# 32u4_devboard_v10.net
KiCad netlist of a schematic drawn in EAGLE
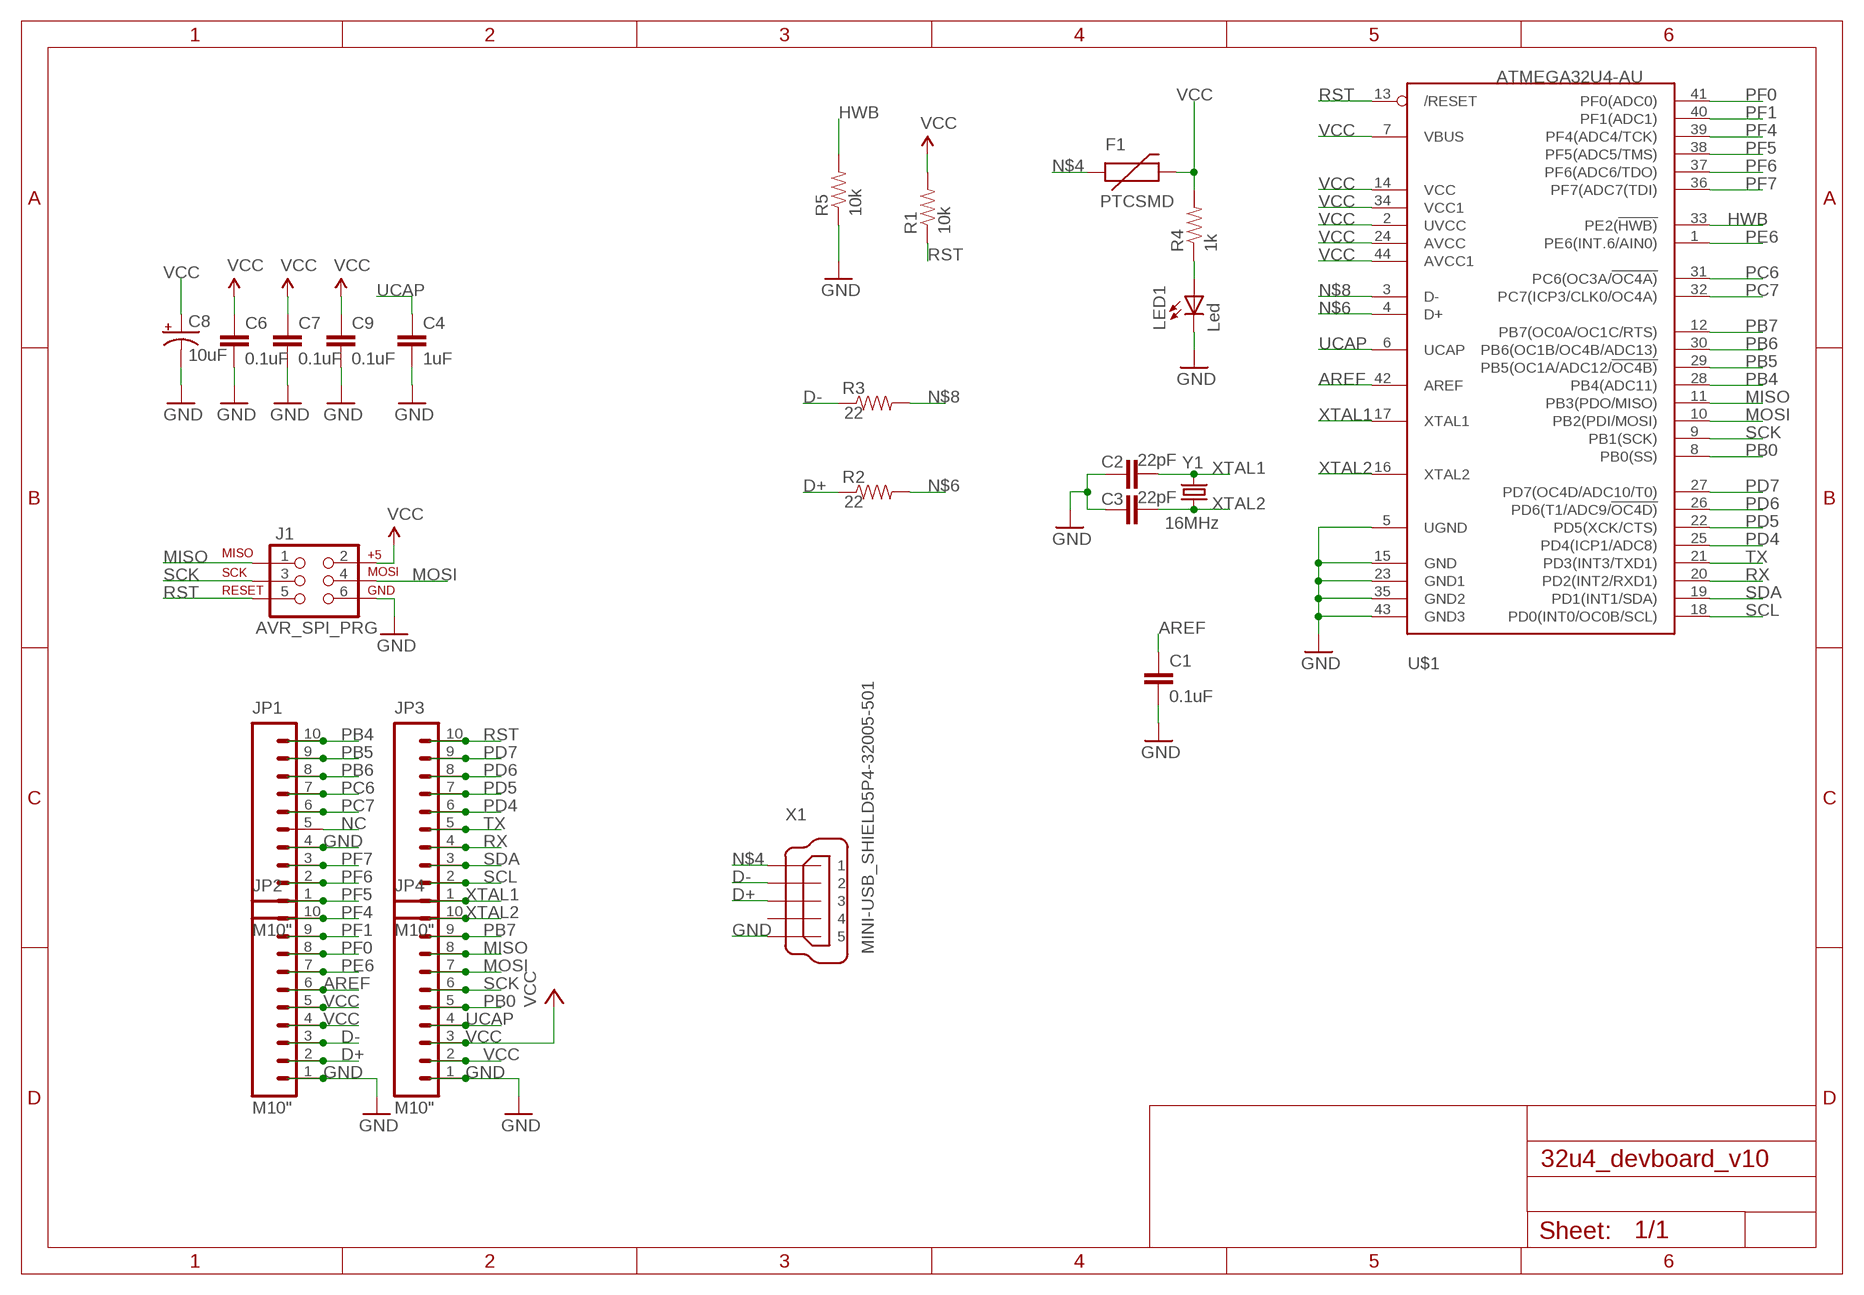
[diagram p0: schematic, sheet 1]

(export (version "E")
  (design (tool "Eeschema 10.0.6"))
  (components
    (comp (ref "C1")
      (value "0.1uF")
      (footprint "eagle-import:0805")
      (libsource (lib "eagle-import") (part "CAP0805"))
    )
    (comp (ref "C2")
      (value "22pF")
      (footprint "eagle-import:0603-CAP")
      (libsource (lib "eagle-import") (part "CAP0603-CAP"))
    )
    (comp (ref "C3")
      (value "22pF")
      (footprint "eagle-import:0603-CAP")
      (libsource (lib "eagle-import") (part "CAP0603-CAP"))
    )
    (comp (ref "C4")
      (value "1uF")
      (footprint "eagle-import:0805")
      (libsource (lib "eagle-import") (part "CAP0805"))
    )
    (comp (ref "C6")
      (value "0.1uF")
      (footprint "eagle-import:0805")
      (libsource (lib "eagle-import") (part "CAP0805"))
    )
    (comp (ref "C7")
      (value "0.1uF")
      (footprint "eagle-import:0805")
      (libsource (lib "eagle-import") (part "CAP0805"))
    )
    (comp (ref "C8")
      (value "10uF")
      (footprint "eagle-import:EIA3216")
      (libsource (lib "eagle-import") (part "CAP_POL1206"))
    )
    (comp (ref "C9")
      (value "0.1uF")
      (footprint "eagle-import:0805")
      (libsource (lib "eagle-import") (part "CAP0805"))
    )
    (comp (ref "F1")
      (value "PTCSMD")
      (footprint "eagle-import:PTC-1206")
      (libsource (lib "eagle-import") (part "PTCSMD"))
    )
    (comp (ref "J1")
      (value "AVR_SPI_PRG")
      (footprint "eagle-import:2X3")
      (libsource (lib "eagle-import") (part "AVR_SPI_PRG_6PTH"))
    )
    (comp (ref "JP1")
      (value "M10\"")
      (footprint "eagle-import:1X10")
      (libsource (lib "eagle-import") (part "M10{dblquote}"))
    )
    (comp (ref "JP2")
      (value "M10\"")
      (footprint "eagle-import:1X10")
      (libsource (lib "eagle-import") (part "M10{dblquote}"))
    )
    (comp (ref "JP3")
      (value "M10\"")
      (footprint "eagle-import:1X10")
      (libsource (lib "eagle-import") (part "M10{dblquote}"))
    )
    (comp (ref "JP4")
      (value "M10\"")
      (footprint "eagle-import:1X10")
      (libsource (lib "eagle-import") (part "M10{dblquote}"))
    )
    (comp (ref "LED1")
      (value "Led")
      (footprint "eagle-import:CHIP-LED0805")
      (libsource (lib "eagle-import") (part "LEDCHIP-LED0805"))
    )
    (comp (ref "R1")
      (value "10k")
      (footprint "eagle-import:0805")
      (libsource (lib "eagle-import") (part "RESISTOR0805-RES"))
    )
    (comp (ref "R2")
      (value "22")
      (footprint "eagle-import:0805")
      (libsource (lib "eagle-import") (part "RESISTOR0805-RES"))
    )
    (comp (ref "R3")
      (value "22")
      (footprint "eagle-import:0805")
      (libsource (lib "eagle-import") (part "RESISTOR0805-RES"))
    )
    (comp (ref "R4")
      (value "1k")
      (footprint "eagle-import:0805")
      (libsource (lib "eagle-import") (part "RESISTOR0805-RES"))
    )
    (comp (ref "R5")
      (value "10k")
      (footprint "eagle-import:0805")
      (libsource (lib "eagle-import") (part "RESISTOR0805-RES"))
    )
    (comp (ref "U$1")
      (value "ATMEGA32U4-AU")
      (footprint "eagle-import:TQFP44")
      (libsource (lib "eagle-import") (part "ATMEGA32U4-AU"))
    )
    (comp (ref "X1")
      (value "MINI-USB_SHIELD5P4-32005-501")
      (footprint "eagle-import:32005-501")
      (libsource (lib "eagle-import") (part "MINI-USB_SHIELD5P4-32005-501"))
    )
    (comp (ref "Y1")
      (value "16MHz")
      (footprint "eagle-import:HC49US")
      (libsource (lib "eagle-import") (part "CRYSTALHC49US"))
    )
  )
  (nets
    (net (code "1") (name "/AREF") (class "Default")
      (node (ref "C1") (pin "1") (pinfunction "1_1") (pintype "passive"))
      (node (ref "JP2") (pin "6") (pinfunction "6_6") (pintype "passive"))
      (node (ref "U$1") (pin "42") (pinfunction "AREF_42") (pintype "bidirectional"))
    )
    (net (code "2") (name "/D+") (class "Default")
      (node (ref "JP2") (pin "2") (pinfunction "2_2") (pintype "passive"))
      (node (ref "R2") (pin "1") (pinfunction "1_1") (pintype "passive"))
      (node (ref "X1") (pin "3") (pinfunction "3_3") (pintype "passive"))
    )
    (net (code "3") (name "/D-") (class "Default")
      (node (ref "JP2") (pin "3") (pinfunction "3_3") (pintype "passive"))
      (node (ref "R3") (pin "1") (pinfunction "1_1") (pintype "passive"))
      (node (ref "X1") (pin "2") (pinfunction "2_2") (pintype "passive"))
    )
    (net (code "4") (name "/HWB") (class "Default")
      (node (ref "R5") (pin "2") (pinfunction "2_2") (pintype "passive"))
      (node (ref "U$1") (pin "33") (pinfunction "PE2(~{HWB})_33") (pintype "bidirectional"))
    )
    (net (code "5") (name "/MISO") (class "Default")
      (node (ref "J1") (pin "1") (pinfunction "1_1") (pintype "passive"))
      (node (ref "JP4") (pin "8") (pinfunction "8_8") (pintype "passive"))
      (node (ref "U$1") (pin "11") (pinfunction "PB3(PDO/MISO)_11") (pintype "bidirectional"))
    )
    (net (code "6") (name "/MOSI") (class "Default")
      (node (ref "J1") (pin "4") (pinfunction "4_4") (pintype "passive"))
      (node (ref "JP4") (pin "7") (pinfunction "7_7") (pintype "passive"))
      (node (ref "U$1") (pin "10") (pinfunction "PB2(PDI/MOSI)_10") (pintype "bidirectional"))
    )
    (net (code "7") (name "/N$4") (class "Default")
      (node (ref "F1") (pin "1") (pinfunction "1_1") (pintype "bidirectional"))
      (node (ref "X1") (pin "1") (pinfunction "1_1") (pintype "passive"))
    )
    (net (code "8") (name "/N$6") (class "Default")
      (node (ref "R2") (pin "2") (pinfunction "2_2") (pintype "passive"))
      (node (ref "U$1") (pin "4") (pinfunction "D+_4") (pintype "bidirectional"))
    )
    (net (code "9") (name "/N$8") (class "Default")
      (node (ref "R3") (pin "2") (pinfunction "2_2") (pintype "passive"))
      (node (ref "U$1") (pin "3") (pinfunction "D-_3") (pintype "bidirectional"))
    )
    (net (code "10") (name "/NC") (class "Default")
      (node (ref "JP1") (pin "5") (pinfunction "5_5") (pintype "passive"))
    )
    (net (code "11") (name "/PB0") (class "Default")
      (node (ref "JP4") (pin "5") (pinfunction "5_5") (pintype "passive"))
      (node (ref "U$1") (pin "8") (pinfunction "PB0(SS)_8") (pintype "bidirectional"))
    )
    (net (code "12") (name "/PB4") (class "Default")
      (node (ref "JP1") (pin "10") (pinfunction "10_10") (pintype "passive"))
      (node (ref "U$1") (pin "28") (pinfunction "PB4(ADC11)_28") (pintype "bidirectional"))
    )
    (net (code "13") (name "/PB5") (class "Default")
      (node (ref "JP1") (pin "9") (pinfunction "9_9") (pintype "passive"))
      (node (ref "U$1") (pin "29") (pinfunction "PB5(OC1A/ADC12/~{OC4B})_29") (pintype "bidirectional"))
    )
    (net (code "14") (name "/PB6") (class "Default")
      (node (ref "JP1") (pin "8") (pinfunction "8_8") (pintype "passive"))
      (node (ref "U$1") (pin "30") (pinfunction "PB6(OC1B/OC4B/ADC13)_30") (pintype "bidirectional"))
    )
    (net (code "15") (name "/PB7") (class "Default")
      (node (ref "JP4") (pin "9") (pinfunction "9_9") (pintype "passive"))
      (node (ref "U$1") (pin "12") (pinfunction "PB7(OC0A/OC1C/RTS)_12") (pintype "bidirectional"))
    )
    (net (code "16") (name "/PC6") (class "Default")
      (node (ref "JP1") (pin "7") (pinfunction "7_7") (pintype "passive"))
      (node (ref "U$1") (pin "31") (pinfunction "PC6(OC3A/~{OC4A})_31") (pintype "bidirectional"))
    )
    (net (code "17") (name "/PC7") (class "Default")
      (node (ref "JP1") (pin "6") (pinfunction "6_6") (pintype "passive"))
      (node (ref "U$1") (pin "32") (pinfunction "PC7(ICP3/CLK0/OC4A)_32") (pintype "bidirectional"))
    )
    (net (code "18") (name "/PD4") (class "Default")
      (node (ref "JP3") (pin "6") (pinfunction "6_6") (pintype "passive"))
      (node (ref "U$1") (pin "25") (pinfunction "PD4(ICP1/ADC8)_25") (pintype "bidirectional"))
    )
    (net (code "19") (name "/PD5") (class "Default")
      (node (ref "JP3") (pin "7") (pinfunction "7_7") (pintype "passive"))
      (node (ref "U$1") (pin "22") (pinfunction "PD5(XCK/CTS)_22") (pintype "bidirectional"))
    )
    (net (code "20") (name "/PD6") (class "Default")
      (node (ref "JP3") (pin "8") (pinfunction "8_8") (pintype "passive"))
      (node (ref "U$1") (pin "26") (pinfunction "PD6(T1/ADC9/~{OC4D})_26") (pintype "bidirectional"))
    )
    (net (code "21") (name "/PD7") (class "Default")
      (node (ref "JP3") (pin "9") (pinfunction "9_9") (pintype "passive"))
      (node (ref "U$1") (pin "27") (pinfunction "PD7(OC4D/ADC10/T0)_27") (pintype "bidirectional"))
    )
    (net (code "22") (name "/PE6") (class "Default")
      (node (ref "JP2") (pin "7") (pinfunction "7_7") (pintype "passive"))
      (node (ref "U$1") (pin "1") (pinfunction "PE6(INT.6/AIN0)_1") (pintype "bidirectional"))
    )
    (net (code "23") (name "/PF0") (class "Default")
      (node (ref "JP2") (pin "8") (pinfunction "8_8") (pintype "passive"))
      (node (ref "U$1") (pin "41") (pinfunction "PF0(ADC0)_41") (pintype "bidirectional"))
    )
    (net (code "24") (name "/PF1") (class "Default")
      (node (ref "JP2") (pin "9") (pinfunction "9_9") (pintype "passive"))
      (node (ref "U$1") (pin "40") (pinfunction "PF1(ADC1)_40") (pintype "bidirectional"))
    )
    (net (code "25") (name "/PF4") (class "Default")
      (node (ref "JP2") (pin "10") (pinfunction "10_10") (pintype "passive"))
      (node (ref "U$1") (pin "39") (pinfunction "PF4(ADC4/TCK)_39") (pintype "bidirectional"))
    )
    (net (code "26") (name "/PF5") (class "Default")
      (node (ref "JP1") (pin "1") (pinfunction "1_1") (pintype "passive"))
      (node (ref "U$1") (pin "38") (pinfunction "PF5(ADC5/TMS)_38") (pintype "bidirectional"))
    )
    (net (code "27") (name "/PF6") (class "Default")
      (node (ref "JP1") (pin "2") (pinfunction "2_2") (pintype "passive"))
      (node (ref "U$1") (pin "37") (pinfunction "PF6(ADC6/TDO)_37") (pintype "bidirectional"))
    )
    (net (code "28") (name "/PF7") (class "Default")
      (node (ref "JP1") (pin "3") (pinfunction "3_3") (pintype "passive"))
      (node (ref "U$1") (pin "36") (pinfunction "PF7(ADC7(TDI)_36") (pintype "bidirectional"))
    )
    (net (code "29") (name "/RST") (class "Default")
      (node (ref "J1") (pin "5") (pinfunction "5_5") (pintype "passive"))
      (node (ref "JP3") (pin "10") (pinfunction "10_10") (pintype "passive"))
      (node (ref "R1") (pin "1") (pinfunction "1_1") (pintype "passive"))
      (node (ref "U$1") (pin "13") (pinfunction "/RESET_13") (pintype "bidirectional"))
    )
    (net (code "30") (name "/RX") (class "Default")
      (node (ref "JP3") (pin "4") (pinfunction "4_4") (pintype "passive"))
      (node (ref "U$1") (pin "20") (pinfunction "PD2(INT2/RXD1)_20") (pintype "bidirectional"))
    )
    (net (code "31") (name "/SCK") (class "Default")
      (node (ref "J1") (pin "3") (pinfunction "3_3") (pintype "passive"))
      (node (ref "JP4") (pin "6") (pinfunction "6_6") (pintype "passive"))
      (node (ref "U$1") (pin "9") (pinfunction "PB1(SCK)_9") (pintype "bidirectional"))
    )
    (net (code "32") (name "/SCL") (class "Default")
      (node (ref "JP3") (pin "2") (pinfunction "2_2") (pintype "passive"))
      (node (ref "U$1") (pin "18") (pinfunction "PD0(INT0/OC0B/SCL)_18") (pintype "bidirectional"))
    )
    (net (code "33") (name "/SDA") (class "Default")
      (node (ref "JP3") (pin "3") (pinfunction "3_3") (pintype "passive"))
      (node (ref "U$1") (pin "19") (pinfunction "PD1(INT1/SDA)_19") (pintype "bidirectional"))
    )
    (net (code "34") (name "/TX") (class "Default")
      (node (ref "JP3") (pin "5") (pinfunction "5_5") (pintype "passive"))
      (node (ref "U$1") (pin "21") (pinfunction "PD3(INT3/TXD1)_21") (pintype "bidirectional"))
    )
    (net (code "35") (name "/UCAP") (class "Default")
      (node (ref "C4") (pin "1") (pinfunction "1_1") (pintype "passive"))
      (node (ref "JP4") (pin "4") (pinfunction "4_4") (pintype "passive"))
      (node (ref "U$1") (pin "6") (pinfunction "UCAP_6") (pintype "bidirectional"))
    )
    (net (code "36") (name "/XTAL1") (class "Default")
      (node (ref "C2") (pin "2") (pinfunction "2_2") (pintype "passive"))
      (node (ref "JP3") (pin "1") (pinfunction "1_1") (pintype "passive"))
      (node (ref "U$1") (pin "17") (pinfunction "XTAL1_17") (pintype "bidirectional"))
      (node (ref "Y1") (pin "2") (pinfunction "2_2") (pintype "passive"))
    )
    (net (code "37") (name "/XTAL2") (class "Default")
      (node (ref "C3") (pin "2") (pinfunction "2_2") (pintype "passive"))
      (node (ref "JP4") (pin "10") (pinfunction "10_10") (pintype "passive"))
      (node (ref "U$1") (pin "16") (pinfunction "XTAL2_16") (pintype "bidirectional"))
      (node (ref "Y1") (pin "1") (pinfunction "1_1") (pintype "passive"))
    )
    (net (code "38") (name "GND") (class "Default")
      (node (ref "C1") (pin "2") (pinfunction "2_2") (pintype "passive"))
      (node (ref "C2") (pin "1") (pinfunction "1_1") (pintype "passive"))
      (node (ref "C3") (pin "1") (pinfunction "1_1") (pintype "passive"))
      (node (ref "C4") (pin "2") (pinfunction "2_2") (pintype "passive"))
      (node (ref "C6") (pin "2") (pinfunction "2_2") (pintype "passive"))
      (node (ref "C7") (pin "2") (pinfunction "2_2") (pintype "passive"))
      (node (ref "C8") (pin "C") (pinfunction "-_C") (pintype "passive"))
      (node (ref "C9") (pin "2") (pinfunction "2_2") (pintype "passive"))
      (node (ref "J1") (pin "6") (pinfunction "6_6") (pintype "passive"))
      (node (ref "JP1") (pin "4") (pinfunction "4_4") (pintype "passive"))
      (node (ref "JP2") (pin "1") (pinfunction "1_1") (pintype "passive"))
      (node (ref "JP4") (pin "1") (pinfunction "1_1") (pintype "passive"))
      (node (ref "LED1") (pin "C") (pinfunction "C_C") (pintype "passive"))
      (node (ref "R5") (pin "1") (pinfunction "1_1") (pintype "passive"))
      (node (ref "U$1") (pin "15") (pinfunction "GND_15") (pintype "bidirectional"))
      (node (ref "U$1") (pin "23") (pinfunction "GND1_23") (pintype "bidirectional"))
      (node (ref "U$1") (pin "35") (pinfunction "GND2_35") (pintype "bidirectional"))
      (node (ref "U$1") (pin "43") (pinfunction "GND3_43") (pintype "bidirectional"))
      (node (ref "U$1") (pin "5") (pinfunction "UGND_5") (pintype "bidirectional"))
      (node (ref "X1") (pin "5") (pinfunction "5_5") (pintype "passive"))
    )
    (net (code "39") (name "Net-(LED1-PadA)") (class "Default")
      (node (ref "LED1") (pin "A") (pinfunction "A_A") (pintype "passive"))
      (node (ref "R4") (pin "1") (pinfunction "1_1") (pintype "passive"))
    )
    (net (code "40") (name "VCC") (class "Default")
      (node (ref "C6") (pin "1") (pinfunction "1_1") (pintype "passive"))
      (node (ref "C7") (pin "1") (pinfunction "1_1") (pintype "passive"))
      (node (ref "C8") (pin "A") (pinfunction "+_A") (pintype "passive"))
      (node (ref "C9") (pin "1") (pinfunction "1_1") (pintype "passive"))
      (node (ref "F1") (pin "2") (pinfunction "2_2") (pintype "bidirectional"))
      (node (ref "J1") (pin "2") (pinfunction "2_2") (pintype "passive"))
      (node (ref "JP2") (pin "4") (pinfunction "4_4") (pintype "passive"))
      (node (ref "JP2") (pin "5") (pinfunction "5_5") (pintype "passive"))
      (node (ref "JP4") (pin "2") (pinfunction "2_2") (pintype "passive"))
      (node (ref "JP4") (pin "3") (pinfunction "3_3") (pintype "passive"))
      (node (ref "R1") (pin "2") (pinfunction "2_2") (pintype "passive"))
      (node (ref "R4") (pin "2") (pinfunction "2_2") (pintype "passive"))
      (node (ref "U$1") (pin "14") (pinfunction "VCC_14") (pintype "bidirectional"))
      (node (ref "U$1") (pin "2") (pinfunction "UVCC_2") (pintype "bidirectional"))
      (node (ref "U$1") (pin "24") (pinfunction "AVCC_24") (pintype "bidirectional"))
      (node (ref "U$1") (pin "34") (pinfunction "VCC1_34") (pintype "bidirectional"))
      (node (ref "U$1") (pin "44") (pinfunction "AVCC1_44") (pintype "bidirectional"))
      (node (ref "U$1") (pin "7") (pinfunction "VBUS_7") (pintype "bidirectional"))
    )
    (net (code "41") (name "unconnected-(X1-Pad4)") (class "Default")
      (node (ref "X1") (pin "4") (pinfunction "4_4") (pintype "passive"))
    )
  )
)
